# milton.net
KiCad netlist of a schematic drawn in EAGLE
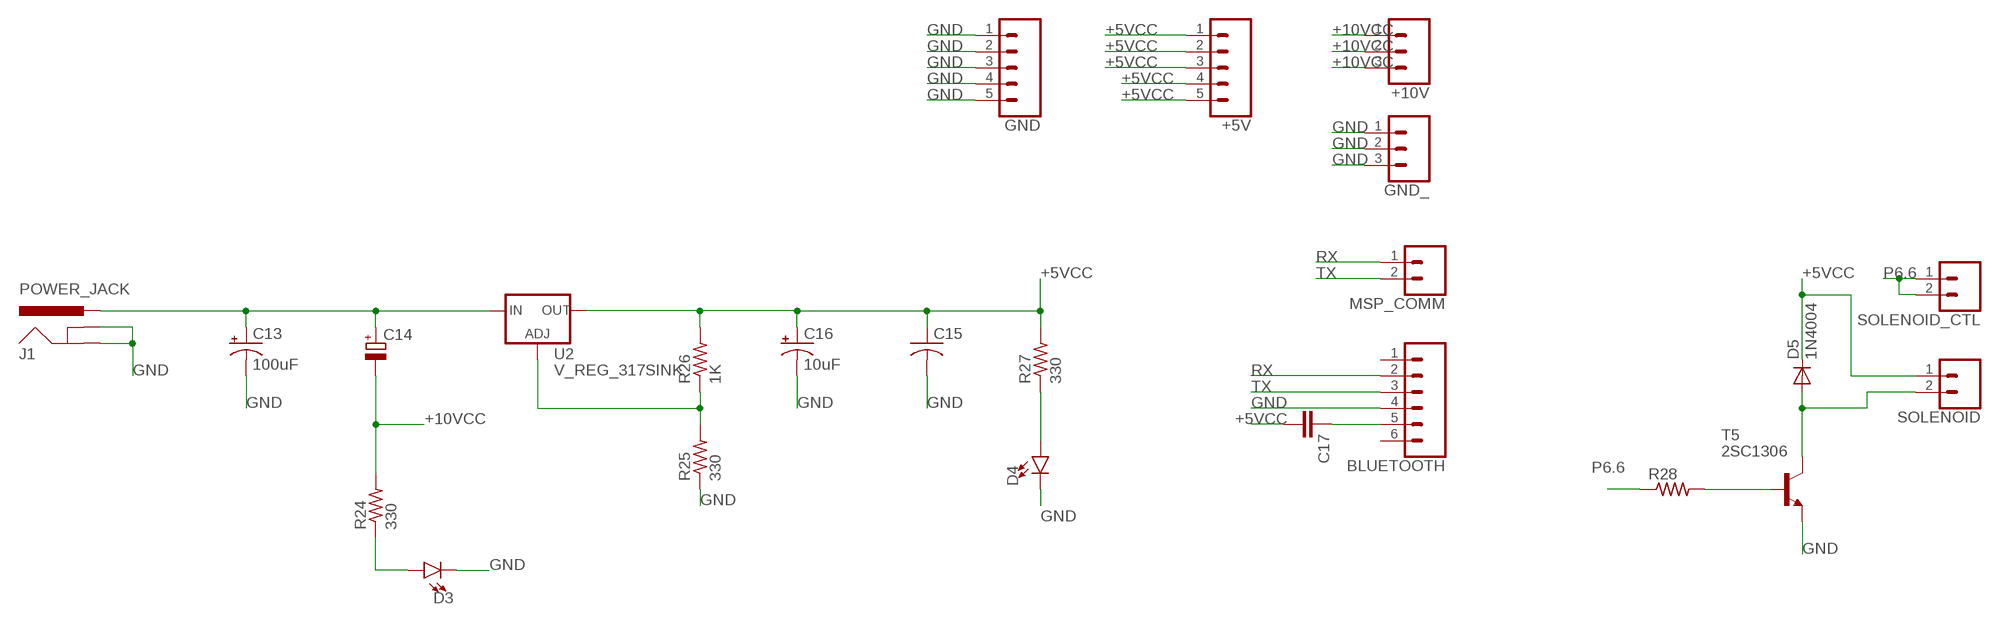
[diagram p0: schematic, sheet 1]

(export (version "E")
  (design (tool "Eeschema 10.0.6"))
  (components
    (comp (ref "+5V")
      (value "CONN_05")
      (footprint "eagle-import:1X05")
      (libsource (lib "eagle-import") (part "CONN_05"))
    )
    (comp (ref "+10V")
      (value "CONN_03")
      (footprint "eagle-import:1X03")
      (libsource (lib "eagle-import") (part "CONN_03"))
    )
    (comp (ref "BLUETOOTH")
      (value "CONN_06SILK_FEMALE_PTH")
      (footprint "eagle-import:1X06")
      (libsource (lib "eagle-import") (part "CONN_06SILK_FEMALE_PTH"))
    )
    (comp (ref "C13")
      (value "100uF")
      (footprint "eagle-import:CPOL-RADIAL-2.5MM-6.5MM")
      (libsource (lib "eagle-import") (part "100UF-POLAR-RADIAL-2.5MM-25V-20%"))
    )
    (comp (ref "C14")
      (value "CPOL-EUE5-6")
      (footprint "eagle-import:E5-6")
      (libsource (lib "eagle-import") (part "CPOL-EUE5-6"))
    )
    (comp (ref "C15")
      (value "C-US050-030X075")
      (footprint "eagle-import:C050-030X075")
      (libsource (lib "eagle-import") (part "C-US050-030X075"))
    )
    (comp (ref "C16")
      (value "10uF")
      (footprint "eagle-import:CPOL-RADIAL-2.5MM-5MM")
      (libsource (lib "eagle-import") (part "10UF-POLAR-RADIAL-2.5MM-25V-20%"))
    )
    (comp (ref "C17")
      (value "C5/3")
      (footprint "eagle-import:C5B3")
      (libsource (lib "eagle-import") (part "C5/3"))
    )
    (comp (ref "D3")
      (value "LED-RED1206")
      (footprint "eagle-import:LED-1206")
      (libsource (lib "eagle-import") (part "LED-RED1206"))
    )
    (comp (ref "D4")
      (value "LED-RED1206")
      (footprint "eagle-import:LED-1206")
      (libsource (lib "eagle-import") (part "LED-RED1206"))
    )
    (comp (ref "D5")
      (value "1N4004")
      (footprint "eagle-import:DO41-10")
      (libsource (lib "eagle-import") (part "1N4004"))
    )
    (comp (ref "GND")
      (value "CONN_05")
      (footprint "eagle-import:1X05")
      (libsource (lib "eagle-import") (part "CONN_05"))
    )
    (comp (ref "GND_")
      (value "CONN_03")
      (footprint "eagle-import:1X03")
      (libsource (lib "eagle-import") (part "CONN_03"))
    )
    (comp (ref "J1")
      (value "POWER_JACK")
      (footprint "eagle-import:POWER_JACK_PTH")
      (libsource (lib "eagle-import") (part "POWER_JACK"))
    )
    (comp (ref "MSP_COMM")
      (value "CONN_02")
      (footprint "eagle-import:1X02")
      (libsource (lib "eagle-import") (part "CONN_02"))
    )
    (comp (ref "R24")
      (value "330")
      (footprint "eagle-import:0207_10")
      (libsource (lib "eagle-import") (part "R-US_0207/10"))
    )
    (comp (ref "R25")
      (value "330")
      (footprint "eagle-import:0207_10")
      (libsource (lib "eagle-import") (part "R-US_0207/10"))
    )
    (comp (ref "R26")
      (value "1K")
      (footprint "eagle-import:0207_10")
      (libsource (lib "eagle-import") (part "R-US_0207/10"))
    )
    (comp (ref "R27")
      (value "330")
      (footprint "eagle-import:0207_10")
      (libsource (lib "eagle-import") (part "R-US_0207/10"))
    )
    (comp (ref "R28")
      (value "R-US_0207/10")
      (footprint "eagle-import:0207_10")
      (libsource (lib "eagle-import") (part "R-US_0207/10"))
    )
    (comp (ref "SOLENOID")
      (value "CONN_02")
      (footprint "eagle-import:1X02")
      (libsource (lib "eagle-import") (part "CONN_02"))
    )
    (comp (ref "SOLENOID_CTL")
      (value "CONN_02")
      (footprint "eagle-import:1X02")
      (libsource (lib "eagle-import") (part "CONN_02"))
    )
    (comp (ref "T5")
      (value "2SC1306")
      (footprint "eagle-import:TO220BV")
      (libsource (lib "eagle-import") (part "2SC1306"))
    )
    (comp (ref "U2")
      (value "V_REG_317SINK")
      (footprint "eagle-import:TO220-ADJ")
      (libsource (lib "eagle-import") (part "V_REG_317SINK"))
    )
  )
  (nets
    (net (code "1") (name "/+5VCC") (class "Default")
      (node (ref "+5V") (pin "1") (pinfunction "1_1") (pintype "passive"))
      (node (ref "+5V") (pin "2") (pinfunction "2_2") (pintype "passive"))
      (node (ref "+5V") (pin "3") (pinfunction "3_3") (pintype "passive"))
      (node (ref "+5V") (pin "4") (pinfunction "4_4") (pintype "passive"))
      (node (ref "+5V") (pin "5") (pinfunction "5_5") (pintype "passive"))
      (node (ref "C15") (pin "1") (pinfunction "1_1") (pintype "passive"))
      (node (ref "C16") (pin "1") (pinfunction "+_1") (pintype "passive"))
      (node (ref "C17") (pin "2") (pinfunction "2_2") (pintype "passive"))
      (node (ref "D5") (pin "C") (pinfunction "C_C") (pintype "passive"))
      (node (ref "R26") (pin "2") (pinfunction "2_2") (pintype "passive"))
      (node (ref "R27") (pin "2") (pinfunction "2_2") (pintype "passive"))
      (node (ref "SOLENOID") (pin "1") (pinfunction "1_1") (pintype "passive"))
      (node (ref "U2") (pin "OUT") (pinfunction "OUT_OUT") (pintype "output"))
    )
    (net (code "2") (name "/+10VCC") (class "Default")
      (node (ref "+10V") (pin "1") (pinfunction "1_1") (pintype "passive"))
      (node (ref "+10V") (pin "2") (pinfunction "2_2") (pintype "passive"))
      (node (ref "+10V") (pin "3") (pinfunction "3_3") (pintype "passive"))
      (node (ref "C14") (pin "-") (pinfunction "-_-") (pintype "passive"))
      (node (ref "R24") (pin "2") (pinfunction "2_2") (pintype "passive"))
    )
    (net (code "3") (name "/GND") (class "Default")
      (node (ref "BLUETOOTH") (pin "4") (pinfunction "4_4") (pintype "passive"))
      (node (ref "C13") (pin "2") (pinfunction "-_2") (pintype "passive"))
      (node (ref "C15") (pin "2") (pinfunction "2_2") (pintype "passive"))
      (node (ref "C16") (pin "2") (pinfunction "-_2") (pintype "passive"))
      (node (ref "D3") (pin "C") (pinfunction "C_C") (pintype "passive"))
      (node (ref "D4") (pin "C") (pinfunction "C_C") (pintype "passive"))
      (node (ref "GND") (pin "1") (pinfunction "1_1") (pintype "passive"))
      (node (ref "GND") (pin "2") (pinfunction "2_2") (pintype "passive"))
      (node (ref "GND") (pin "3") (pinfunction "3_3") (pintype "passive"))
      (node (ref "GND") (pin "4") (pinfunction "4_4") (pintype "passive"))
      (node (ref "GND") (pin "5") (pinfunction "5_5") (pintype "passive"))
      (node (ref "GND_") (pin "1") (pinfunction "1_1") (pintype "passive"))
      (node (ref "GND_") (pin "2") (pinfunction "2_2") (pintype "passive"))
      (node (ref "GND_") (pin "3") (pinfunction "3_3") (pintype "passive"))
      (node (ref "J1") (pin "GND") (pinfunction "GND_GND") (pintype "bidirectional"))
      (node (ref "J1") (pin "GNDBREAK") (pinfunction "GNDBREAK_GNDBREAK") (pintype "bidirectional"))
      (node (ref "R25") (pin "1") (pinfunction "1_1") (pintype "passive"))
      (node (ref "T5") (pin "3") (pinfunction "E_3") (pintype "passive"))
    )
    (net (code "4") (name "/P6.6") (class "Default")
      (node (ref "R28") (pin "1") (pinfunction "1_1") (pintype "passive"))
      (node (ref "SOLENOID_CTL") (pin "1") (pinfunction "1_1") (pintype "passive"))
      (node (ref "SOLENOID_CTL") (pin "2") (pinfunction "2_2") (pintype "passive"))
    )
    (net (code "5") (name "/RX") (class "Default")
      (node (ref "BLUETOOTH") (pin "2") (pinfunction "2_2") (pintype "passive"))
      (node (ref "MSP_COMM") (pin "1") (pinfunction "1_1") (pintype "passive"))
    )
    (net (code "6") (name "/TX") (class "Default")
      (node (ref "BLUETOOTH") (pin "3") (pinfunction "3_3") (pintype "passive"))
      (node (ref "MSP_COMM") (pin "2") (pinfunction "2_2") (pintype "passive"))
    )
    (net (code "7") (name "Net-(BLUETOOTH-Pad5)") (class "Default")
      (node (ref "BLUETOOTH") (pin "5") (pinfunction "5_5") (pintype "passive"))
      (node (ref "C17") (pin "1") (pinfunction "1_1") (pintype "passive"))
    )
    (net (code "8") (name "Net-(C13-+)") (class "Default")
      (node (ref "C13") (pin "1") (pinfunction "+_1") (pintype "passive"))
      (node (ref "C14") (pin "+") (pinfunction "+_+") (pintype "passive"))
      (node (ref "J1") (pin "PWR") (pinfunction "PWR_PWR") (pintype "bidirectional"))
      (node (ref "U2") (pin "IN") (pinfunction "IN_IN") (pintype "input"))
    )
    (net (code "9") (name "Net-(D3-PadA)") (class "Default")
      (node (ref "D3") (pin "A") (pinfunction "A_A") (pintype "passive"))
      (node (ref "R24") (pin "1") (pinfunction "1_1") (pintype "passive"))
    )
    (net (code "10") (name "Net-(D4-PadA)") (class "Default")
      (node (ref "D4") (pin "A") (pinfunction "A_A") (pintype "passive"))
      (node (ref "R27") (pin "1") (pinfunction "1_1") (pintype "passive"))
    )
    (net (code "11") (name "Net-(R25-Pad2)") (class "Default")
      (node (ref "R25") (pin "2") (pinfunction "2_2") (pintype "passive"))
      (node (ref "R26") (pin "1") (pinfunction "1_1") (pintype "passive"))
      (node (ref "U2") (pin "ADJ") (pinfunction "ADJ_ADJ") (pintype "input"))
    )
    (net (code "12") (name "Net-(T5-B)") (class "Default")
      (node (ref "R28") (pin "2") (pinfunction "2_2") (pintype "passive"))
      (node (ref "T5") (pin "1") (pinfunction "B_1") (pintype "passive"))
    )
    (net (code "13") (name "Net-(T5-C)") (class "Default")
      (node (ref "D5") (pin "A") (pinfunction "A_A") (pintype "passive"))
      (node (ref "SOLENOID") (pin "2") (pinfunction "2_2") (pintype "passive"))
      (node (ref "T5") (pin "2") (pinfunction "C_2") (pintype "passive"))
    )
    (net (code "14") (name "unconnected-(BLUETOOTH-Pad1)") (class "Default")
      (node (ref "BLUETOOTH") (pin "1") (pinfunction "1_1") (pintype "passive"))
    )
    (net (code "15") (name "unconnected-(BLUETOOTH-Pad6)") (class "Default")
      (node (ref "BLUETOOTH") (pin "6") (pinfunction "6_6") (pintype "passive"))
    )
  )
)
